# OSHW-RGB-Badge_v10.net
KiCad netlist of a schematic drawn in EAGLE
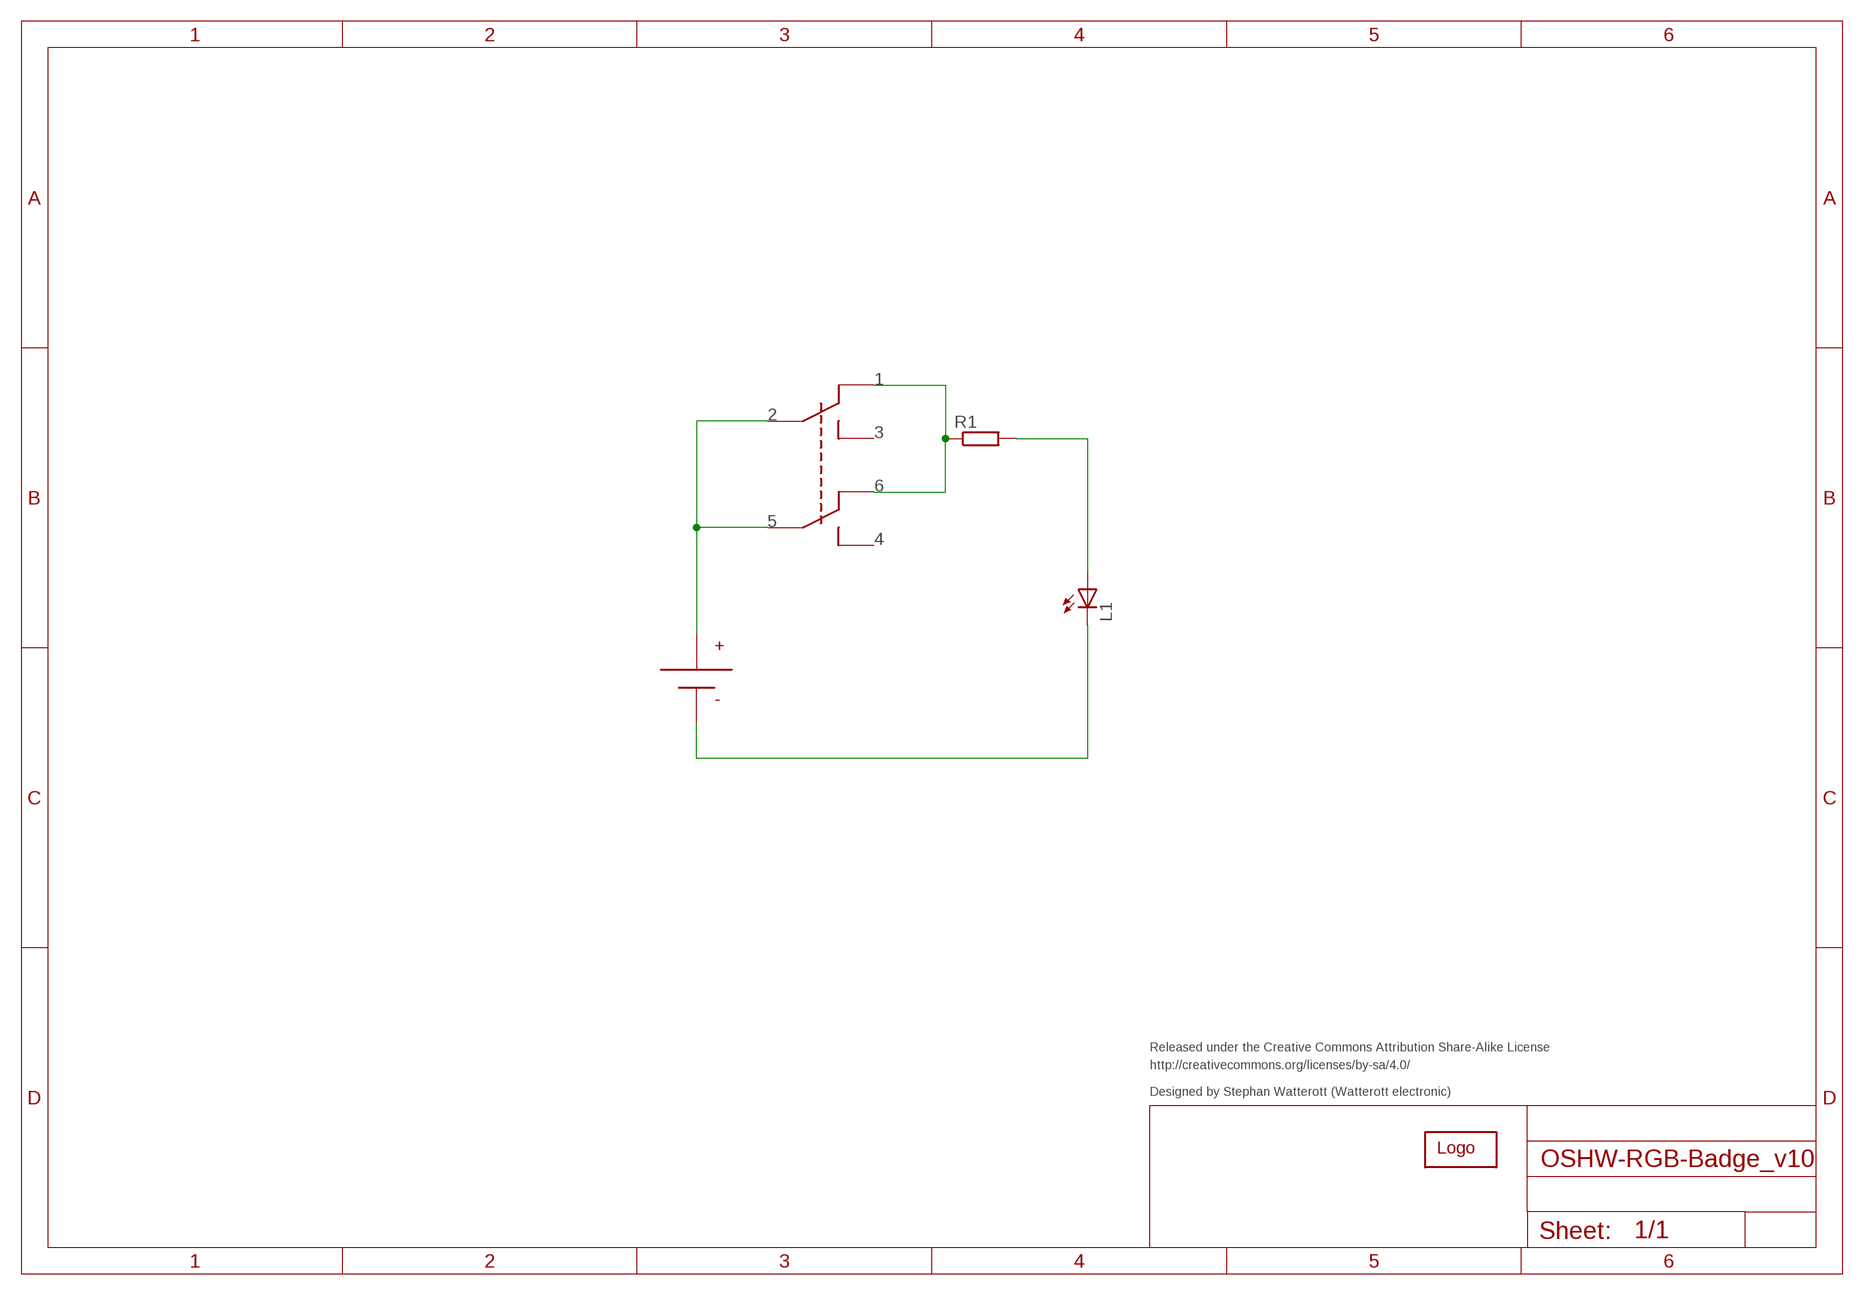
[diagram p0: schematic, sheet 1]

(export (version "E")
  (design (tool "Eeschema 10.0.6"))
  (components
    (comp (ref "L1")
      (value "LED10MM")
      (footprint "eagle-import:LED10MM")
      (libsource (lib "eagle-import") (part "LED10MM"))
    )
    (comp (ref "LOGO1")
      (value "LOGOPLACE")
      (footprint "eagle-import:LOGO_TPLACE")
      (libsource (lib "eagle-import") (part "LOGOPLACE"))
    )
    (comp (ref "R1")
      (value "R-EU_0207/7")
      (footprint "eagle-import:0207_7")
      (libsource (lib "eagle-import") (part "R-EU_0207/7"))
    )
    (comp (ref "SW")
      (value "SWITCH_6-POL_RM2.54")
      (footprint "eagle-import:SWITCH_6POL_RM2.54")
      (libsource (lib "eagle-import") (part "SWITCH_6-POL_RM2.54"))
    )
    (comp (ref "U$1")
      (value "CN2032_BATTERY_HOLDER")
      (footprint "eagle-import:CN2032_BATTERY_HOLDER")
      (libsource (lib "eagle-import") (part "CN2032_BATTERY_HOLDER"))
    )
  )
  (nets
    (net (code "1") (name "Net-(L1-C)") (class "Default")
      (node (ref "L1") (pin "K") (pinfunction "C_K") (pintype "passive"))
      (node (ref "U$1") (pin "P$2") (pinfunction "-_P$2") (pintype "bidirectional"))
    )
    (net (code "2") (name "Net-(L1-PadA)") (class "Default")
      (node (ref "L1") (pin "A") (pinfunction "A_A") (pintype "passive"))
      (node (ref "R1") (pin "2") (pinfunction "2_2") (pintype "passive"))
    )
    (net (code "3") (name "Net-(R1-Pad1)") (class "Default")
      (node (ref "R1") (pin "1") (pinfunction "1_1") (pintype "passive"))
      (node (ref "SW") (pin "P$1") (pinfunction "P$1_P$1") (pintype "bidirectional"))
      (node (ref "SW") (pin "P$6") (pinfunction "P$6_P$6") (pintype "bidirectional"))
    )
    (net (code "4") (name "Net-(U$1-+)") (class "Default")
      (node (ref "SW") (pin "P$2") (pinfunction "P$2_P$2") (pintype "bidirectional"))
      (node (ref "SW") (pin "P$5") (pinfunction "P$5_P$5") (pintype "bidirectional"))
      (node (ref "U$1") (pin "P$1") (pinfunction "+_P$1") (pintype "bidirectional"))
    )
    (net (code "5") (name "unconnected-(SW-PadP$3)") (class "Default")
      (node (ref "SW") (pin "P$3") (pinfunction "P$3_P$3") (pintype "bidirectional"))
    )
    (net (code "6") (name "unconnected-(SW-PadP$4)") (class "Default")
      (node (ref "SW") (pin "P$4") (pinfunction "P$4_P$4") (pintype "bidirectional"))
    )
  )
)
